# 32u4_Gripper_Shield.net
KiCad netlist of a schematic drawn in EAGLE
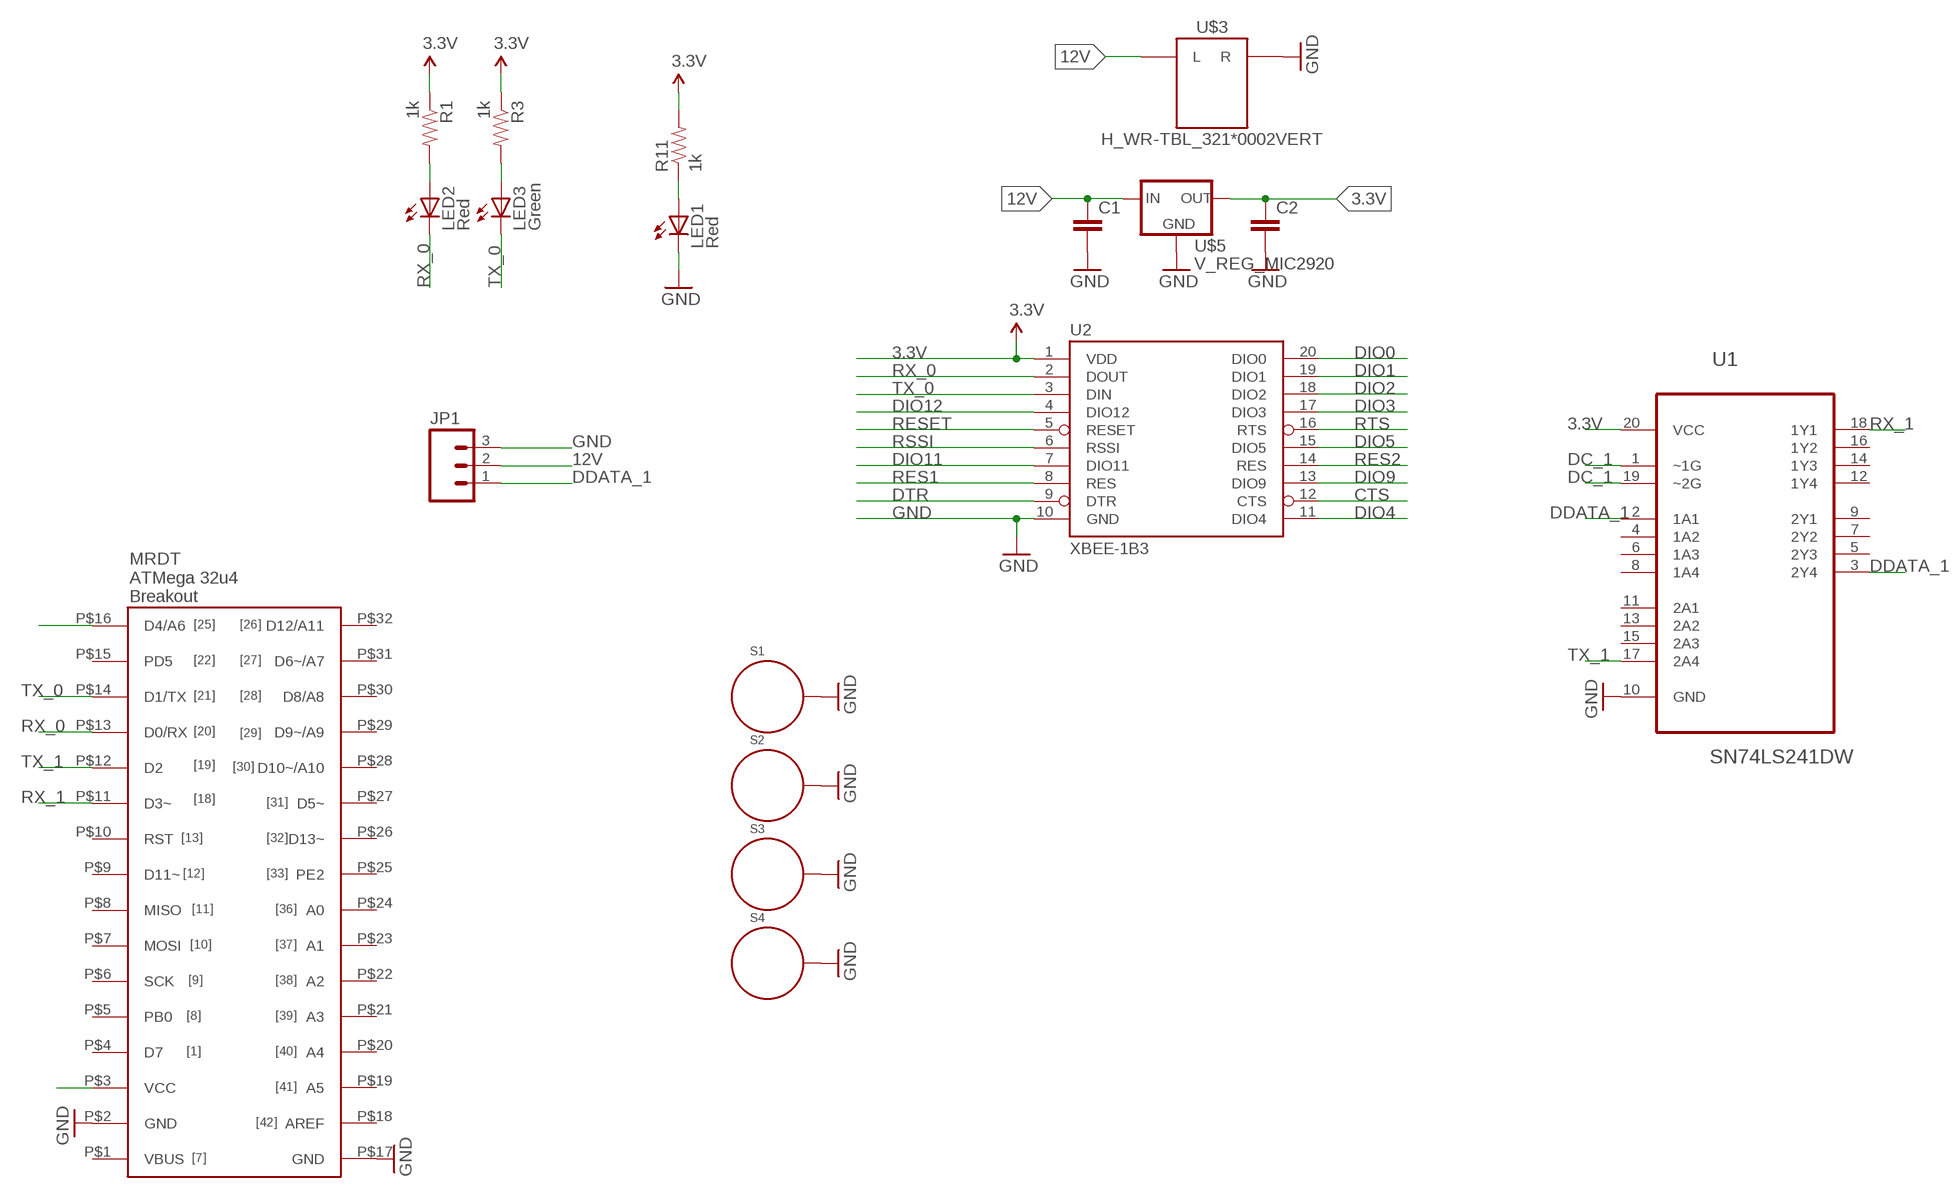
[diagram p0: schematic, sheet 1]

(export (version "E")
  (design (tool "Eeschema 10.0.6"))
  (components
    (comp (ref "C1")
      (value "CAP1206")
      (footprint "eagle-import:1206")
      (libsource (lib "eagle-import") (part "CAP1206"))
    )
    (comp (ref "C2")
      (value "CAP1206")
      (footprint "eagle-import:1206")
      (libsource (lib "eagle-import") (part "CAP1206"))
    )
    (comp (ref "JP1")
      (value "M03PTH")
      (footprint "eagle-import:1X03")
      (libsource (lib "eagle-import") (part "M03PTH"))
    )
    (comp (ref "LED1")
      (value "Red")
      (footprint "eagle-import:LED-0603")
      (libsource (lib "eagle-import") (part "LED0603"))
    )
    (comp (ref "LED2")
      (value "Red")
      (footprint "eagle-import:LED-0603")
      (libsource (lib "eagle-import") (part "LED0603"))
    )
    (comp (ref "LED3")
      (value "Green")
      (footprint "eagle-import:LED-0603")
      (libsource (lib "eagle-import") (part "LED0603"))
    )
    (comp (ref "R1")
      (value "1k")
      (footprint "eagle-import:1206")
      (libsource (lib "eagle-import") (part "RESISTOR1206"))
    )
    (comp (ref "R3")
      (value "1k")
      (footprint "eagle-import:1206")
      (libsource (lib "eagle-import") (part "RESISTOR1206"))
    )
    (comp (ref "R11")
      (value "1k")
      (footprint "eagle-import:1206")
      (libsource (lib "eagle-import") (part "RESISTOR1206"))
    )
    (comp (ref "S1")
      (value "STANDOFF_ELECTRICAL")
      (footprint "eagle-import:STANDOFF-ELECTRICAL")
      (libsource (lib "eagle-import") (part "STANDOFF_ELECTRICAL"))
    )
    (comp (ref "S2")
      (value "STANDOFF_ELECTRICAL")
      (footprint "eagle-import:STANDOFF-ELECTRICAL")
      (libsource (lib "eagle-import") (part "STANDOFF_ELECTRICAL"))
    )
    (comp (ref "S3")
      (value "STANDOFF_ELECTRICAL")
      (footprint "eagle-import:STANDOFF-ELECTRICAL")
      (libsource (lib "eagle-import") (part "STANDOFF_ELECTRICAL"))
    )
    (comp (ref "S4")
      (value "STANDOFF_ELECTRICAL")
      (footprint "eagle-import:STANDOFF-ELECTRICAL")
      (libsource (lib "eagle-import") (part "STANDOFF_ELECTRICAL"))
    )
    (comp (ref "U$1")
      (value "32U4_BREAKOU_SMD")
      (footprint "eagle-import:32U3_MCU_DIP_SMD")
      (libsource (lib "eagle-import") (part "32U4_BREAKOU_SMD"))
    )
    (comp (ref "U$3")
      (value "H_WR-TBL_321*0002VERT")
      (footprint "eagle-import:691321100002")
      (libsource (lib "eagle-import") (part "H_WR-TBL_3210002VERT"))
    )
    (comp (ref "U$5")
      (value "V_REG_MIC2920")
      (footprint "eagle-import:SOT223")
      (libsource (lib "eagle-import") (part "V_REG_MIC2920"))
    )
    (comp (ref "U1")
      (value "SN74LS241DW")
      (footprint "eagle-import:SOIC127P1030X265-20N")
      (libsource (lib "eagle-import") (part "SN74LS241DW"))
    )
    (comp (ref "U2")
      (value "XBEE-1B3")
      (footprint "eagle-import:XBEE-SMD")
      (libsource (lib "eagle-import") (part "XBEE-1B3"))
    )
  )
  (nets
    (net (code "1") (name "/CTS") (class "Default")
      (node (ref "U2") (pin "12") (pinfunction "CTS_12") (pintype "output"))
    )
    (net (code "2") (name "/DC_1") (class "Default")
      (node (ref "U$1") (pin "P$16") (pinfunction "D4/A6_P$16") (pintype "bidirectional"))
      (node (ref "U1") (pin "1") (pinfunction "~{1G}_1") (pintype "input"))
      (node (ref "U1") (pin "19") (pinfunction "~{2G}_19") (pintype "input"))
    )
    (net (code "3") (name "/DDATA_1") (class "Default")
      (node (ref "JP1") (pin "1") (pinfunction "1_1") (pintype "passive"))
      (node (ref "U1") (pin "2") (pinfunction "1A1_2") (pintype "input"))
      (node (ref "U1") (pin "3") (pinfunction "2Y4_3") (pintype "output"))
    )
    (net (code "4") (name "/DIO0") (class "Default")
      (node (ref "U2") (pin "20") (pinfunction "DIO0_20") (pintype "bidirectional"))
    )
    (net (code "5") (name "/DIO1") (class "Default")
      (node (ref "U2") (pin "19") (pinfunction "DIO1_19") (pintype "bidirectional"))
    )
    (net (code "6") (name "/DIO2") (class "Default")
      (node (ref "U2") (pin "18") (pinfunction "DIO2_18") (pintype "bidirectional"))
    )
    (net (code "7") (name "/DIO3") (class "Default")
      (node (ref "U2") (pin "17") (pinfunction "DIO3_17") (pintype "bidirectional"))
    )
    (net (code "8") (name "/DIO4") (class "Default")
      (node (ref "U2") (pin "11") (pinfunction "DIO4_11") (pintype "bidirectional"))
    )
    (net (code "9") (name "/DIO5") (class "Default")
      (node (ref "U2") (pin "15") (pinfunction "DIO5_15") (pintype "bidirectional"))
    )
    (net (code "10") (name "/DIO9") (class "Default")
      (node (ref "U2") (pin "13") (pinfunction "DIO9_13") (pintype "bidirectional"))
    )
    (net (code "11") (name "/DIO11") (class "Default")
      (node (ref "U2") (pin "7") (pinfunction "DIO11_7") (pintype "bidirectional"))
    )
    (net (code "12") (name "/DIO12") (class "Default")
      (node (ref "U2") (pin "4") (pinfunction "DIO12_4") (pintype "bidirectional"))
    )
    (net (code "13") (name "/DTR") (class "Default")
      (node (ref "U2") (pin "9") (pinfunction "DTR_9") (pintype "bidirectional"))
    )
    (net (code "14") (name "/RES1") (class "Default")
      (node (ref "U2") (pin "8") (pinfunction "RES_8") (pintype "bidirectional"))
    )
    (net (code "15") (name "/RES2") (class "Default")
      (node (ref "U2") (pin "14") (pinfunction "RES_14") (pintype "bidirectional"))
    )
    (net (code "16") (name "/RESET") (class "Default")
      (node (ref "U2") (pin "5") (pinfunction "RESET_5") (pintype "input"))
    )
    (net (code "17") (name "/RSSI") (class "Default")
      (node (ref "U2") (pin "6") (pinfunction "RSSI_6") (pintype "bidirectional"))
    )
    (net (code "18") (name "/RTS") (class "Default")
      (node (ref "U2") (pin "16") (pinfunction "RTS_16") (pintype "input"))
    )
    (net (code "19") (name "/RX_0") (class "Default")
      (node (ref "LED2") (pin "C") (pinfunction "C_C") (pintype "passive"))
      (node (ref "U$1") (pin "P$13") (pinfunction "D0/RX_P$13") (pintype "bidirectional"))
      (node (ref "U2") (pin "2") (pinfunction "DOUT_2") (pintype "output"))
    )
    (net (code "20") (name "/RX_1") (class "Default")
      (node (ref "U$1") (pin "P$11") (pinfunction "D3~{}_P$11") (pintype "bidirectional"))
      (node (ref "U1") (pin "18") (pinfunction "1Y1_18") (pintype "output"))
    )
    (net (code "21") (name "/TX_0") (class "Default")
      (node (ref "LED3") (pin "C") (pinfunction "C_C") (pintype "passive"))
      (node (ref "U$1") (pin "P$14") (pinfunction "D1/TX_P$14") (pintype "bidirectional"))
      (node (ref "U2") (pin "3") (pinfunction "DIN_3") (pintype "input"))
    )
    (net (code "22") (name "/TX_1") (class "Default")
      (node (ref "U$1") (pin "P$12") (pinfunction "D2_P$12") (pintype "bidirectional"))
      (node (ref "U1") (pin "17") (pinfunction "2A4_17") (pintype "input"))
    )
    (net (code "23") (name "3.3V") (class "Default")
      (node (ref "C2") (pin "1") (pinfunction "1_1") (pintype "passive"))
      (node (ref "R1") (pin "1") (pinfunction "1_1") (pintype "passive"))
      (node (ref "R11") (pin "2") (pinfunction "2_2") (pintype "passive"))
      (node (ref "R3") (pin "1") (pinfunction "1_1") (pintype "passive"))
      (node (ref "U$1") (pin "P$3") (pinfunction "VCC_P$3") (pintype "bidirectional"))
      (node (ref "U$5") (pin "3") (pinfunction "OUT_3") (pintype "output"))
      (node (ref "U1") (pin "20") (pinfunction "VCC_20") (pintype "power_in"))
      (node (ref "U2") (pin "1") (pinfunction "VDD_1") (pintype "power_in"))
    )
    (net (code "24") (name "12V") (class "Default")
      (node (ref "C1") (pin "1") (pinfunction "1_1") (pintype "passive"))
      (node (ref "JP1") (pin "2") (pinfunction "2_2") (pintype "passive"))
      (node (ref "U$3") (pin "L") (pinfunction "L_L") (pintype "bidirectional"))
      (node (ref "U$5") (pin "1") (pinfunction "IN_1") (pintype "input"))
    )
    (net (code "25") (name "GND") (class "Default")
      (node (ref "C1") (pin "2") (pinfunction "2_2") (pintype "passive"))
      (node (ref "C2") (pin "2") (pinfunction "2_2") (pintype "passive"))
      (node (ref "JP1") (pin "3") (pinfunction "3_3") (pintype "passive"))
      (node (ref "LED1") (pin "C") (pinfunction "C_C") (pintype "passive"))
      (node (ref "S1") (pin "P1") (pinfunction "P$1_P1") (pintype "bidirectional"))
      (node (ref "S2") (pin "P1") (pinfunction "P$1_P1") (pintype "bidirectional"))
      (node (ref "S3") (pin "P1") (pinfunction "P$1_P1") (pintype "bidirectional"))
      (node (ref "S4") (pin "P1") (pinfunction "P$1_P1") (pintype "bidirectional"))
      (node (ref "U$1") (pin "P$17") (pinfunction "GND_P$17") (pintype "bidirectional"))
      (node (ref "U$1") (pin "P$2") (pinfunction "GND_P$2") (pintype "bidirectional"))
      (node (ref "U$3") (pin "R") (pinfunction "R_R") (pintype "bidirectional"))
      (node (ref "U$5") (pin "2") (pinfunction "GND_2") (pintype "input"))
      (node (ref "U$5") (pin "4") (pinfunction "GND_4") (pintype "input"))
      (node (ref "U1") (pin "10") (pinfunction "GND_10") (pintype "passive"))
      (node (ref "U2") (pin "10") (pinfunction "GND_10") (pintype "power_in"))
    )
    (net (code "26") (name "Net-(LED1-PadA)") (class "Default")
      (node (ref "LED1") (pin "A") (pinfunction "A_A") (pintype "passive"))
      (node (ref "R11") (pin "1") (pinfunction "1_1") (pintype "passive"))
    )
    (net (code "27") (name "Net-(LED2-PadA)") (class "Default")
      (node (ref "LED2") (pin "A") (pinfunction "A_A") (pintype "passive"))
      (node (ref "R1") (pin "2") (pinfunction "2_2") (pintype "passive"))
    )
    (net (code "28") (name "Net-(LED3-PadA)") (class "Default")
      (node (ref "LED3") (pin "A") (pinfunction "A_A") (pintype "passive"))
      (node (ref "R3") (pin "2") (pinfunction "2_2") (pintype "passive"))
    )
    (net (code "29") (name "unconnected-(U$1-A0-PadP$24)") (class "Default")
      (node (ref "U$1") (pin "P$24") (pinfunction "A0_P$24") (pintype "bidirectional"))
    )
    (net (code "30") (name "unconnected-(U$1-A1-PadP$23)") (class "Default")
      (node (ref "U$1") (pin "P$23") (pinfunction "A1_P$23") (pintype "bidirectional"))
    )
    (net (code "31") (name "unconnected-(U$1-A2-PadP$22)") (class "Default")
      (node (ref "U$1") (pin "P$22") (pinfunction "A2_P$22") (pintype "bidirectional"))
    )
    (net (code "32") (name "unconnected-(U$1-A3-PadP$21)") (class "Default")
      (node (ref "U$1") (pin "P$21") (pinfunction "A3_P$21") (pintype "bidirectional"))
    )
    (net (code "33") (name "unconnected-(U$1-A4-PadP$20)") (class "Default")
      (node (ref "U$1") (pin "P$20") (pinfunction "A4_P$20") (pintype "bidirectional"))
    )
    (net (code "34") (name "unconnected-(U$1-A5-PadP$19)") (class "Default")
      (node (ref "U$1") (pin "P$19") (pinfunction "A5_P$19") (pintype "bidirectional"))
    )
    (net (code "35") (name "unconnected-(U$1-AREF-PadP$18)") (class "Default")
      (node (ref "U$1") (pin "P$18") (pinfunction "AREF_P$18") (pintype "bidirectional"))
    )
    (net (code "36") (name "unconnected-(U$1-D5~{}-PadP$27)") (class "Default")
      (node (ref "U$1") (pin "P$27") (pinfunction "D5~{}_P$27") (pintype "bidirectional"))
    )
    (net (code "37") (name "unconnected-(U$1-D6~{{slash}A7}-PadP$31)") (class "Default")
      (node (ref "U$1") (pin "P$31") (pinfunction "D6~{/A7}_P$31") (pintype "bidirectional"))
    )
    (net (code "38") (name "unconnected-(U$1-D7-PadP$4)") (class "Default")
      (node (ref "U$1") (pin "P$4") (pinfunction "D7_P$4") (pintype "bidirectional"))
    )
    (net (code "39") (name "unconnected-(U$1-D8{slash}A8-PadP$30)") (class "Default")
      (node (ref "U$1") (pin "P$30") (pinfunction "D8/A8_P$30") (pintype "bidirectional"))
    )
    (net (code "40") (name "unconnected-(U$1-D9~{{slash}A9}-PadP$29)") (class "Default")
      (node (ref "U$1") (pin "P$29") (pinfunction "D9~{/A9}_P$29") (pintype "bidirectional"))
    )
    (net (code "41") (name "unconnected-(U$1-D10~{{slash}A10}-PadP$28)") (class "Default")
      (node (ref "U$1") (pin "P$28") (pinfunction "D10~{/A10}_P$28") (pintype "bidirectional"))
    )
    (net (code "42") (name "unconnected-(U$1-D11~{}-PadP$9)") (class "Default")
      (node (ref "U$1") (pin "P$9") (pinfunction "D11~{}_P$9") (pintype "bidirectional"))
    )
    (net (code "43") (name "unconnected-(U$1-D12{slash}A11-PadP$32)") (class "Default")
      (node (ref "U$1") (pin "P$32") (pinfunction "D12/A11_P$32") (pintype "bidirectional"))
    )
    (net (code "44") (name "unconnected-(U$1-D13~{}-PadP$26)") (class "Default")
      (node (ref "U$1") (pin "P$26") (pinfunction "D13~{}_P$26") (pintype "bidirectional"))
    )
    (net (code "45") (name "unconnected-(U$1-MISO-PadP$8)") (class "Default")
      (node (ref "U$1") (pin "P$8") (pinfunction "MISO_P$8") (pintype "bidirectional"))
    )
    (net (code "46") (name "unconnected-(U$1-MOSI-PadP$7)") (class "Default")
      (node (ref "U$1") (pin "P$7") (pinfunction "MOSI_P$7") (pintype "bidirectional"))
    )
    (net (code "47") (name "unconnected-(U$1-PB0-PadP$5)") (class "Default")
      (node (ref "U$1") (pin "P$5") (pinfunction "PB0_P$5") (pintype "bidirectional"))
    )
    (net (code "48") (name "unconnected-(U$1-PD5-PadP$15)") (class "Default")
      (node (ref "U$1") (pin "P$15") (pinfunction "PD5_P$15") (pintype "bidirectional"))
    )
    (net (code "49") (name "unconnected-(U$1-PE2-PadP$25)") (class "Default")
      (node (ref "U$1") (pin "P$25") (pinfunction "PE2_P$25") (pintype "bidirectional"))
    )
    (net (code "50") (name "unconnected-(U$1-RST-PadP$10)") (class "Default")
      (node (ref "U$1") (pin "P$10") (pinfunction "RST_P$10") (pintype "bidirectional"))
    )
    (net (code "51") (name "unconnected-(U$1-SCK-PadP$6)") (class "Default")
      (node (ref "U$1") (pin "P$6") (pinfunction "SCK_P$6") (pintype "bidirectional"))
    )
    (net (code "52") (name "unconnected-(U$1-VBUS-PadP$1)") (class "Default")
      (node (ref "U$1") (pin "P$1") (pinfunction "VBUS_P$1") (pintype "bidirectional"))
    )
    (net (code "53") (name "unconnected-(U1-1A2-Pad4)") (class "Default")
      (node (ref "U1") (pin "4") (pinfunction "1A2_4") (pintype "input"))
    )
    (net (code "54") (name "unconnected-(U1-1A3-Pad6)") (class "Default")
      (node (ref "U1") (pin "6") (pinfunction "1A3_6") (pintype "input"))
    )
    (net (code "55") (name "unconnected-(U1-1A4-Pad8)") (class "Default")
      (node (ref "U1") (pin "8") (pinfunction "1A4_8") (pintype "input"))
    )
    (net (code "56") (name "unconnected-(U1-1Y2-Pad16)") (class "Default")
      (node (ref "U1") (pin "16") (pinfunction "1Y2_16") (pintype "output"))
    )
    (net (code "57") (name "unconnected-(U1-1Y3-Pad14)") (class "Default")
      (node (ref "U1") (pin "14") (pinfunction "1Y3_14") (pintype "output"))
    )
    (net (code "58") (name "unconnected-(U1-1Y4-Pad12)") (class "Default")
      (node (ref "U1") (pin "12") (pinfunction "1Y4_12") (pintype "output"))
    )
    (net (code "59") (name "unconnected-(U1-2A1-Pad11)") (class "Default")
      (node (ref "U1") (pin "11") (pinfunction "2A1_11") (pintype "input"))
    )
    (net (code "60") (name "unconnected-(U1-2A2-Pad13)") (class "Default")
      (node (ref "U1") (pin "13") (pinfunction "2A2_13") (pintype "input"))
    )
    (net (code "61") (name "unconnected-(U1-2A3-Pad15)") (class "Default")
      (node (ref "U1") (pin "15") (pinfunction "2A3_15") (pintype "input"))
    )
    (net (code "62") (name "unconnected-(U1-2Y1-Pad9)") (class "Default")
      (node (ref "U1") (pin "9") (pinfunction "2Y1_9") (pintype "output"))
    )
    (net (code "63") (name "unconnected-(U1-2Y2-Pad7)") (class "Default")
      (node (ref "U1") (pin "7") (pinfunction "2Y2_7") (pintype "output"))
    )
    (net (code "64") (name "unconnected-(U1-2Y3-Pad5)") (class "Default")
      (node (ref "U1") (pin "5") (pinfunction "2Y3_5") (pintype "output"))
    )
  )
)
